# Beleuchtung_ESP.net
KiCad netlist of a schematic drawn in Altium Designer
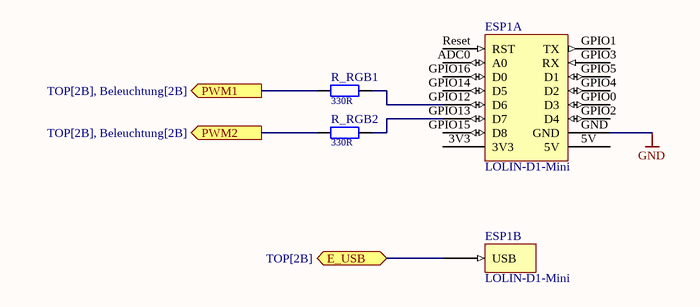
[diagram p0: Beleuchtung_ESP.SchDoc]

(export (version "E")
  (design (tool "Eeschema 10.0.6"))
  (components
    (comp (ref "ESP1") (value "LOLIN-D1-Mini") (libsource (lib "3D_Scanner") (part "LOLIN-D1-Mini")))
    (comp (ref "R_RGB1")
      (value "330R")
      (footprint "R_0207/RM4")
      (description "Resistor")
      (libsource (lib "HTLInn_RLCQ") (part "R"))
    )
    (comp (ref "R_RGB2")
      (value "330R")
      (footprint "R_0207/RM4")
      (description "Resistor")
      (libsource (lib "HTLInn_RLCQ") (part "R"))
    )
  )
  (nets
    (net (code "1") (name "/E_USB") (class "Default")
      (node (ref "ESP1") (pin "") (pinfunction "USB_") (pintype "input"))
    )
    (net (code "2") (name "/PWM1") (class "Default")
      (node (ref "R_RGB1") (pin "2") (pinfunction "2_2") (pintype "passive"))
    )
    (net (code "3") (name "/PWM2") (class "Default")
      (node (ref "R_RGB2") (pin "2") (pinfunction "2_2") (pintype "passive"))
    )
    (net (code "4") (name "GND") (class "Default")
      (node (ref "ESP1") (pin "GND") (pinfunction "GND_GND") (pintype "power_in"))
    )
    (net (code "5") (name "Net-(ESP1A-D6)") (class "Default")
      (node (ref "ESP1") (pin "GPIO12") (pinfunction "D6_GPIO12") (pintype "bidirectional"))
      (node (ref "R_RGB1") (pin "1") (pinfunction "1_1") (pintype "passive"))
    )
    (net (code "6") (name "Net-(ESP1A-D7)") (class "Default")
      (node (ref "ESP1") (pin "GPIO13") (pinfunction "D7_GPIO13") (pintype "bidirectional"))
      (node (ref "R_RGB2") (pin "1") (pinfunction "1_1") (pintype "passive"))
    )
    (net (code "7") (name "unconnected-(ESP1-Pad3V3)") (class "Default")
      (node (ref "ESP1") (pin "3V3") (pinfunction "3V3_3V3") (pintype "power_in"))
    )
    (net (code "8") (name "unconnected-(ESP1-Pad5V)") (class "Default")
      (node (ref "ESP1") (pin "5V") (pinfunction "5V_5V") (pintype "power_in"))
    )
    (net (code "9") (name "unconnected-(ESP1A-A0-PadADC0)") (class "Default")
      (node (ref "ESP1") (pin "ADC0") (pinfunction "A0_ADC0") (pintype "bidirectional"))
    )
    (net (code "10") (name "unconnected-(ESP1A-D0-PadGPIO16)") (class "Default")
      (node (ref "ESP1") (pin "GPIO16") (pinfunction "D0_GPIO16") (pintype "bidirectional"))
    )
    (net (code "11") (name "unconnected-(ESP1A-D1-PadGPIO5)") (class "Default")
      (node (ref "ESP1") (pin "GPIO5") (pinfunction "D1_GPIO5") (pintype "bidirectional"))
    )
    (net (code "12") (name "unconnected-(ESP1A-D2-PadGPIO4)") (class "Default")
      (node (ref "ESP1") (pin "GPIO4") (pinfunction "D2_GPIO4") (pintype "bidirectional"))
    )
    (net (code "13") (name "unconnected-(ESP1A-D3-PadGPIO0)") (class "Default")
      (node (ref "ESP1") (pin "GPIO0") (pinfunction "D3_GPIO0") (pintype "bidirectional"))
    )
    (net (code "14") (name "unconnected-(ESP1A-D4-PadGPIO2)") (class "Default")
      (node (ref "ESP1") (pin "GPIO2") (pinfunction "D4_GPIO2") (pintype "bidirectional"))
    )
    (net (code "15") (name "unconnected-(ESP1A-D5-PadGPIO14)") (class "Default")
      (node (ref "ESP1") (pin "GPIO14") (pinfunction "D5_GPIO14") (pintype "bidirectional"))
    )
    (net (code "16") (name "unconnected-(ESP1A-D8-PadGPIO15)") (class "Default")
      (node (ref "ESP1") (pin "GPIO15") (pinfunction "D8_GPIO15") (pintype "bidirectional"))
    )
    (net (code "17") (name "unconnected-(ESP1A-RST-PadReset)") (class "Default")
      (node (ref "ESP1") (pin "Reset") (pinfunction "RST_Reset") (pintype "input"))
    )
    (net (code "18") (name "unconnected-(ESP1A-RX-PadGPIO3)") (class "Default")
      (node (ref "ESP1") (pin "GPIO3") (pinfunction "RX_GPIO3") (pintype "input"))
    )
    (net (code "19") (name "unconnected-(ESP1A-TX-PadGPIO1)") (class "Default")
      (node (ref "ESP1") (pin "GPIO1") (pinfunction "TX_GPIO1") (pintype "output"))
    )
  )
)
